# usmernowacz.net
KiCad netlist of a schematic drawn in EAGLE
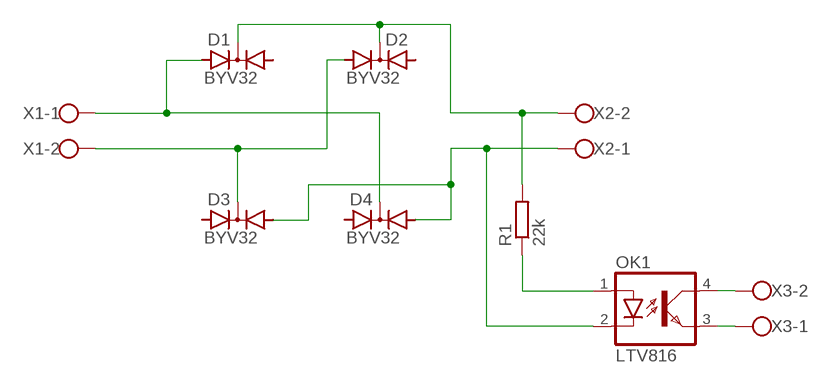
[diagram p0: schematic, sheet 1]

(export (version "E")
  (design (tool "Eeschema 10.0.6"))
  (components
    (comp (ref "D1")
      (value "BYV32")
      (footprint "eagle-import:TO220ABS")
      (libsource (lib "eagle-import") (part "BYV32"))
    )
    (comp (ref "D2")
      (value "BYV32")
      (footprint "eagle-import:TO220ABS")
      (libsource (lib "eagle-import") (part "BYV32"))
    )
    (comp (ref "D3")
      (value "BYV32")
      (footprint "eagle-import:TO220ABS")
      (libsource (lib "eagle-import") (part "BYV32"))
    )
    (comp (ref "D4")
      (value "BYV32")
      (footprint "eagle-import:TO220ABS")
      (libsource (lib "eagle-import") (part "BYV32"))
    )
    (comp (ref "OK1")
      (value "LTV816")
      (footprint "eagle-import:DIL04")
      (libsource (lib "eagle-import") (part "LTV816"))
    )
    (comp (ref "R1")
      (value "22k")
      (footprint "eagle-import:R1206")
      (libsource (lib "eagle-import") (part "R-EU_R1206"))
    )
    (comp (ref "X1")
      (value "W237-102")
      (footprint "eagle-import:W237-102")
      (fields (field (name "MPN") "237-102"))
      (libsource (lib "eagle-import") (part "W237-102"))
    )
    (comp (ref "X2")
      (value "W237-102")
      (footprint "eagle-import:W237-102")
      (fields (field (name "MPN") "237-102"))
      (libsource (lib "eagle-import") (part "W237-102"))
    )
    (comp (ref "X3")
      (value "W237-102")
      (footprint "eagle-import:W237-102")
      (fields (field (name "MPN") "237-102"))
      (libsource (lib "eagle-import") (part "W237-102"))
    )
  )
  (nets
    (net (code "1") (name "Net-(OK1-A)") (class "Default")
      (node (ref "OK1") (pin "1") (pinfunction "A_1") (pintype "passive"))
      (node (ref "R1") (pin "1") (pinfunction "1_1") (pintype "passive"))
    )
    (net (code "2") (name "Net-(OK1-C)") (class "Default")
      (node (ref "D3") (pin "A2") (pinfunction "A2_A2") (pintype "passive"))
      (node (ref "D4") (pin "A2") (pinfunction "A2_A2") (pintype "passive"))
      (node (ref "OK1") (pin "2") (pinfunction "C_2") (pintype "passive"))
      (node (ref "X2") (pin "1") (pinfunction "KL_1") (pintype "passive"))
    )
    (net (code "3") (name "Net-(OK1-COL)") (class "Default")
      (node (ref "OK1") (pin "4") (pinfunction "COL_4") (pintype "passive"))
      (node (ref "X3") (pin "2") (pinfunction "KL_2") (pintype "passive"))
    )
    (net (code "4") (name "Net-(OK1-EMIT)") (class "Default")
      (node (ref "OK1") (pin "3") (pinfunction "EMIT_3") (pintype "passive"))
      (node (ref "X3") (pin "1") (pinfunction "KL_1") (pintype "passive"))
    )
    (net (code "5") (name "Net-(X1A-KL)") (class "Default")
      (node (ref "D1") (pin "A1") (pinfunction "A1_A1") (pintype "passive"))
      (node (ref "D4") (pin "C") (pinfunction "C_C") (pintype "passive"))
      (node (ref "X1") (pin "1") (pinfunction "KL_1") (pintype "passive"))
    )
    (net (code "6") (name "Net-(X1B-KL)") (class "Default")
      (node (ref "D2") (pin "A1") (pinfunction "A1_A1") (pintype "passive"))
      (node (ref "D3") (pin "C") (pinfunction "C_C") (pintype "passive"))
      (node (ref "X1") (pin "2") (pinfunction "KL_2") (pintype "passive"))
    )
    (net (code "7") (name "Net-(X2B-KL)") (class "Default")
      (node (ref "D1") (pin "C") (pinfunction "C_C") (pintype "passive"))
      (node (ref "D2") (pin "C") (pinfunction "C_C") (pintype "passive"))
      (node (ref "R1") (pin "2") (pinfunction "2_2") (pintype "passive"))
      (node (ref "X2") (pin "2") (pinfunction "KL_2") (pintype "passive"))
    )
    (net (code "8") (name "unconnected-(D1-PadA2)") (class "Default")
      (node (ref "D1") (pin "A2") (pinfunction "A2_A2") (pintype "passive"))
    )
    (net (code "9") (name "unconnected-(D2-PadA2)") (class "Default")
      (node (ref "D2") (pin "A2") (pinfunction "A2_A2") (pintype "passive"))
    )
    (net (code "10") (name "unconnected-(D3-PadA1)") (class "Default")
      (node (ref "D3") (pin "A1") (pinfunction "A1_A1") (pintype "passive"))
    )
    (net (code "11") (name "unconnected-(D4-PadA1)") (class "Default")
      (node (ref "D4") (pin "A1") (pinfunction "A1_A1") (pintype "passive"))
    )
  )
)
